# LC_LPF5.net
KiCad netlist of a schematic drawn in Altium Designer
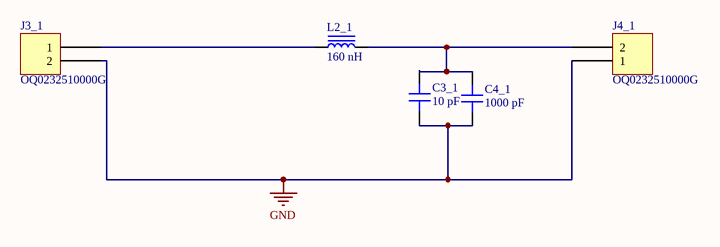
[diagram p0: LC_LPF5.SchDoc]

(export (version "E")
  (design (tool "Eeschema 10.0.6"))
  (components
    (comp (ref "C3_1")
      (value "10 pF")
      (footprint "CAP 0603_1608")
      (description "CAP CER 10PF 100V C0G/NPO 0603")
      (fields (field (name "PART NUMBER") "AC0603JRNPO0BN100") (field (name "MANUFACTURER") "Yageo"))
      (libsource (lib "Celestial Altium Library - altium_library") (part "Capacitor"))
    )
    (comp (ref "C4_1")
      (value "1000 pF")
      (footprint "CAP 0603_1608")
      (description "CAP CER 1000PF 100V X7R 0603")
      (fields
        (field (name "PART NUMBER") "GCD188R72A102KA01D")
        (field (name "MANUFACTURER") "Murata Electronics")
      )
      (libsource (lib "Celestial Altium Library - altium_library") (part "Capacitor"))
    )
    (comp (ref "J3_1")
      (value "OQ0232510000G")
      (footprint "FCI 06-381-2PIN")
      (description "TERM BLOCK HDR 2POS 90DEG 3.81MM")
      (fields (field (name "MANUFACTURER") "Amphenol Anytek"))
      (libsource (lib "") (part "2 Pin_1"))
    )
    (comp (ref "J4_1")
      (value "OQ0232510000G")
      (footprint "FCI 06-381-2PIN")
      (description "TERM BLOCK HDR 2POS 90DEG 3.81MM")
      (fields (field (name "MANUFACTURER") "Amphenol Anytek"))
      (libsource (lib "Celestial Altium Library - altium_library") (part "2 Pin"))
    )
    (comp (ref "L2_1")
      (value "160 nH")
      (footprint "IND 0402_1005 RF WW")
      (description "FIXED IND 160NH 480MA 330MOHM SM")
      (fields
        (field (name "PART NUMBER") "LQW15CNR16J00D")
        (field (name "MANUFACTURER") "Murata Electronics")
      )
      (libsource (lib "Celestial Altium Library - altium_library") (part "Inductor"))
    )
  )
  (nets
    (net (code "1") (name "GND") (class "Default")
      (node (ref "C3_1") (pin "1") (pinfunction "1_1") (pintype "passive"))
      (node (ref "C4_1") (pin "2") (pinfunction "2_2") (pintype "passive"))
      (node (ref "J3_1") (pin "2") (pinfunction "2_2") (pintype "passive"))
      (node (ref "J4_1") (pin "1") (pinfunction "1_1") (pintype "passive"))
    )
    (net (code "2") (name "Net-(C3_1-Pad2)") (class "Default")
      (node (ref "C3_1") (pin "2") (pinfunction "2_2") (pintype "passive"))
      (node (ref "C4_1") (pin "1") (pinfunction "1_1") (pintype "passive"))
      (node (ref "J4_1") (pin "2") (pinfunction "2_2") (pintype "passive"))
      (node (ref "L2_1") (pin "2") (pinfunction "2_2") (pintype "passive"))
    )
    (net (code "3") (name "Net-(J3_1-Pad1)") (class "Default")
      (node (ref "J3_1") (pin "1") (pinfunction "1_1") (pintype "passive"))
      (node (ref "L2_1") (pin "1") (pinfunction "1_1") (pintype "passive"))
    )
  )
)
